# WX0_011_911DL.net
KiCad netlist of a schematic drawn in Altium Designer
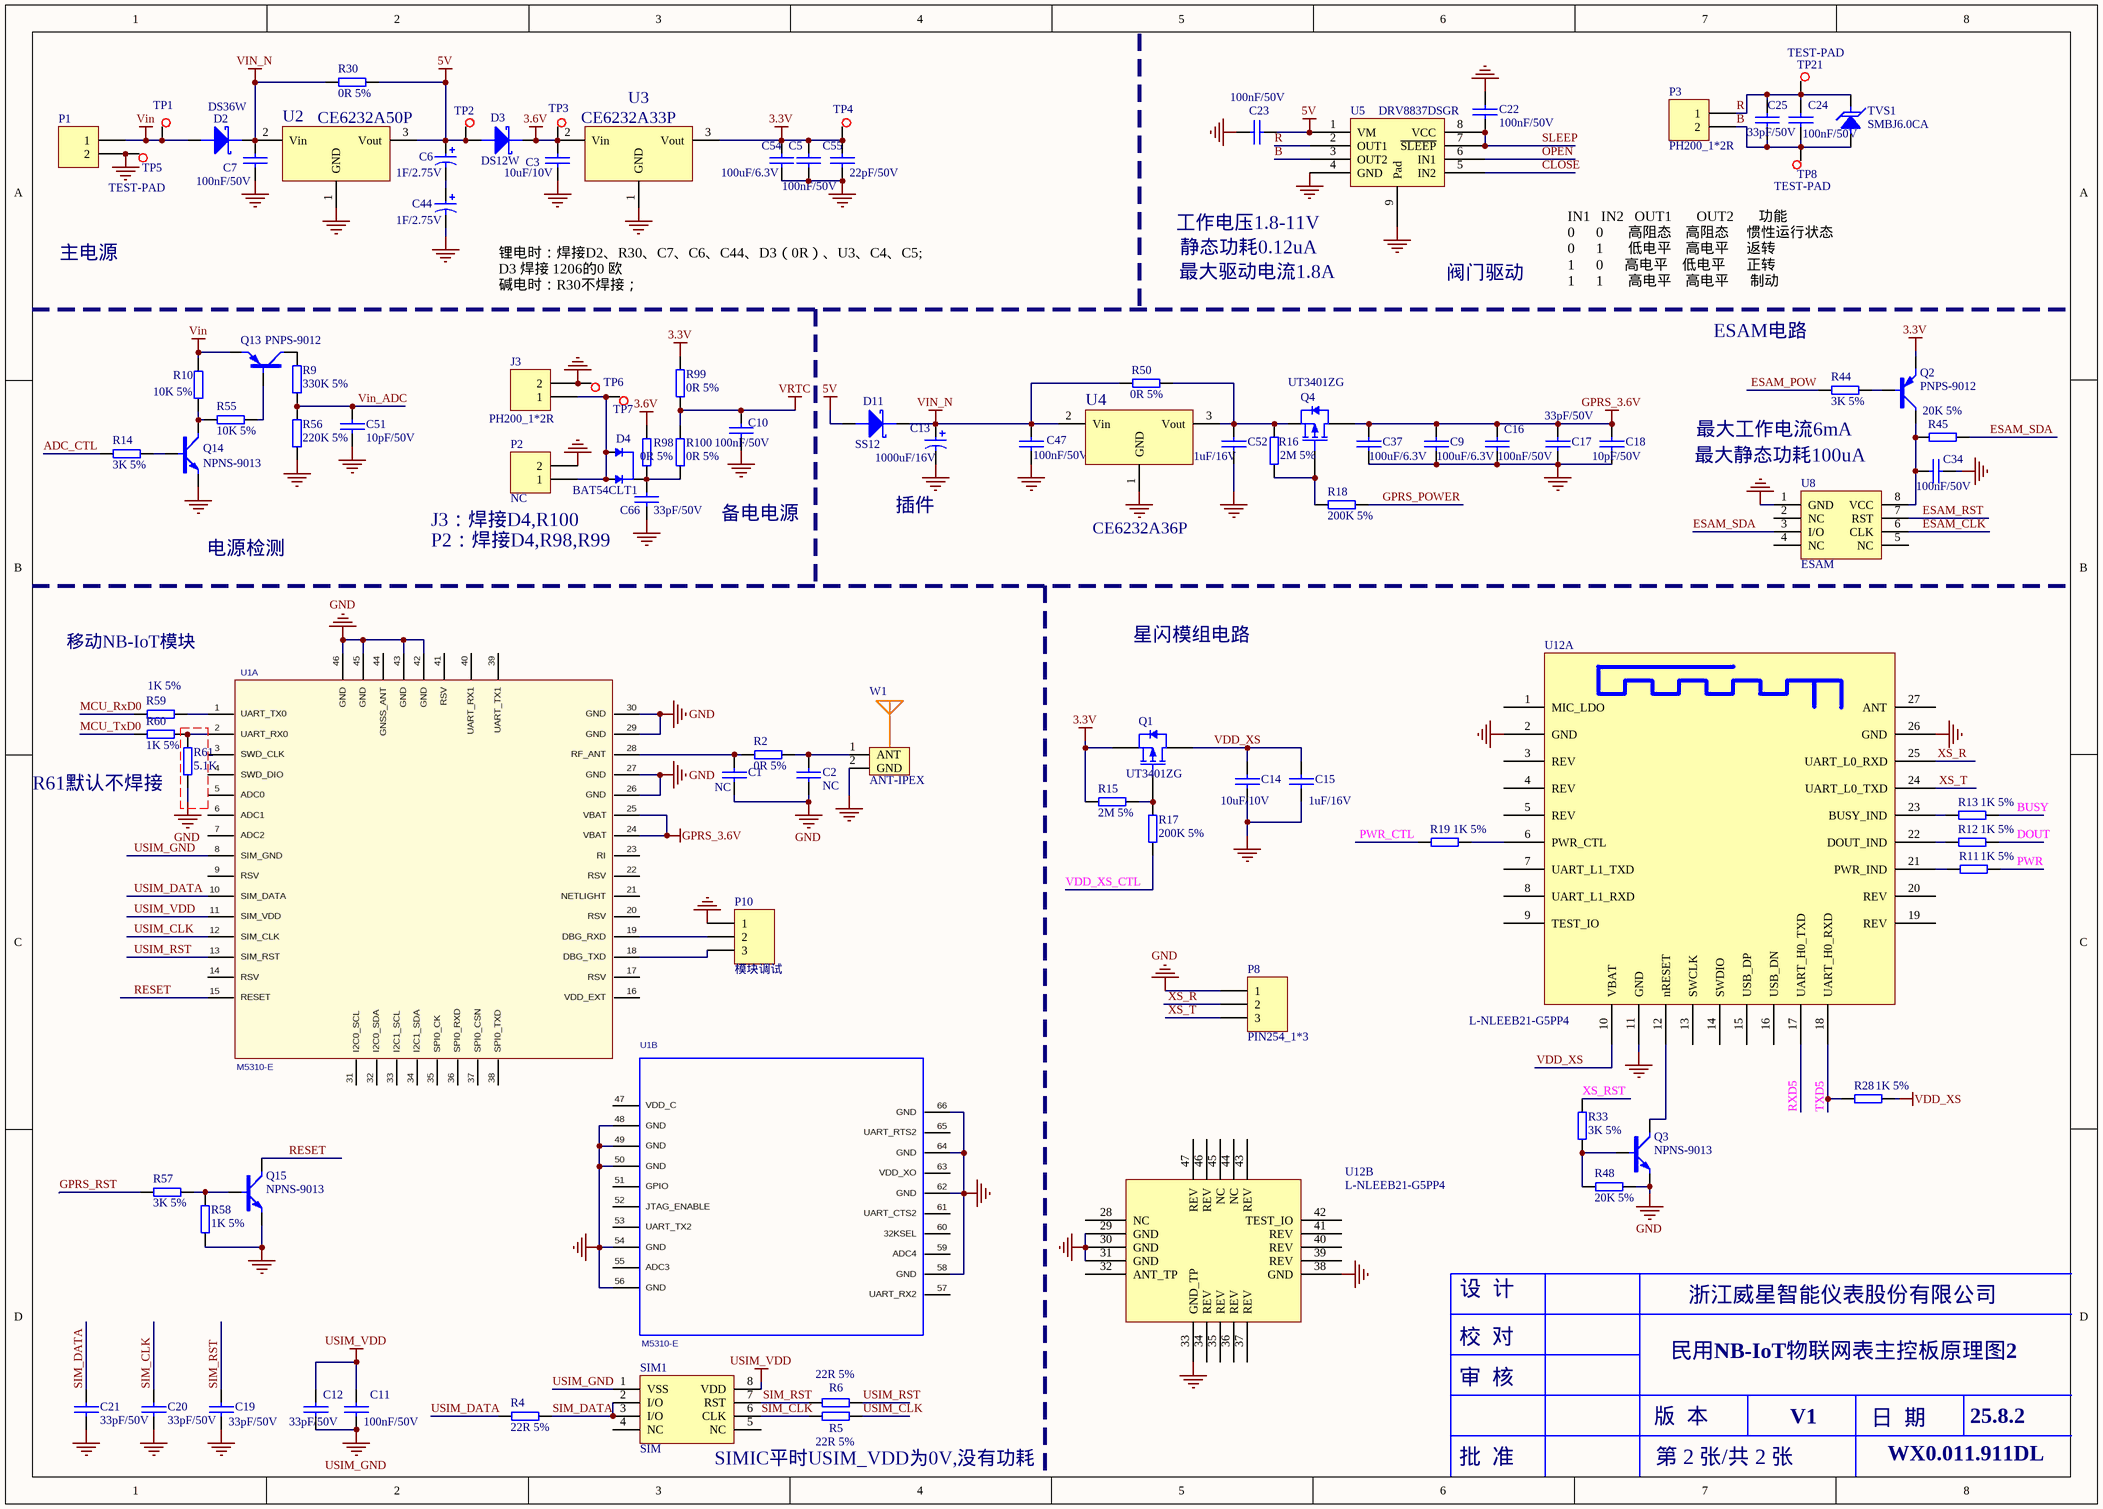
[diagram p0: WX0.011.911DL.SchDoc]

(export (version "E")
  (design (tool "Eeschema 10.0.6"))
  (components
    (comp (ref "C1")
      (value "NC")
      (footprint "CAP0603")
      (description "12P,50 V,±5%,0603,国巨,CC0603JRNPO9BN12")
      (fields (field (name "PART NUMBER") "101020103-0005"))
      (libsource (lib "Database_Libs2") (part "CC03JPO9_12P"))
    )
    (comp (ref "C2")
      (value "NC")
      (footprint "CAP0603")
      (description "12P,50 V,±5%,0603,国巨,CC0603JRNPO9BN12")
      (fields (field (name "PART NUMBER") "101020103-0005"))
      (libsource (lib "Database_Libs2") (part "CC03JPO9_12P"))
    )
    (comp (ref "C3")
      (value "10uF/10V")
      (footprint "CAP0603")
      (description "106pF,10 V,±10%,0603,村田,GRM188R61A106KE47D")
      (fields (field (name "PART NUMBER") "101020103-0026"))
      (libsource (lib "Database_Libs2") (part "CC03K5R6_10U"))
    )
    (comp (ref "C5")
      (value "100nF/50V")
      (footprint "CAP0603")
      (description "104pF,50 V,±10%,0603,国巨,CC0603KRX7R9BB104")
      (fields (field (name "PART NUMBER") "101020103-0021"))
      (libsource (lib "Database_Libs2") (part "CC03K7R9_100N"))
    )
    (comp (ref "C6")
      (value "1F/2.75V")
      (footprint "CAPPC_350_800_1600R")
      (description "1F,2.75 V,-20%~+20%,8mm*16mm,红宝石,2.7 DMC 1 M MY4 8X16")
      (fields (field (name "PART NUMBER") "1010202-0015"))
      (libsource (lib "Database_Libs2") (part "CALM3MRDMC_1F"))
    )
    (comp (ref "C7")
      (value "100nF/50V")
      (footprint "CAP0603")
      (description "104pF,50 V,±10%,0603,国巨,CC0603KRX7R9BB104")
      (fields (field (name "PART NUMBER") "101020103-0021"))
      (libsource (lib "Database_Libs2") (part "CC03K7R9_100N"))
    )
    (comp (ref "C9")
      (value "100uF/6.3V")
      (footprint "GRM1206")
      (description "100uF,6.3 V,±20%,1206,村田,GRM31CR60J107ME39L")
      (fields (field (name "PART NUMBER") "101020101-0020"))
      (libsource (lib "Database_Libs2") (part "CC06M5R5_107P"))
    )
    (comp (ref "C10")
      (value "100nF/50V")
      (footprint "CAP0603")
      (description "104pF,50 V,±10%,0603,国巨,CC0603KRX7R9BB104")
      (fields (field (name "PART NUMBER") "101020103-0021"))
      (libsource (lib "Database_Libs2") (part "CC03K7R9_100N"))
    )
    (comp (ref "C11")
      (value "100nF/50V")
      (footprint "CAP0603")
      (description "104pF,50 V,±10%,0603,国巨,CC0603KRX7R9BB104")
      (fields (field (name "PART NUMBER") "101020103-0021"))
      (libsource (lib "Database_Libs2") (part "CC03K7R9_100N"))
    )
    (comp (ref "C12")
      (value "33pF/50V")
      (footprint "CAP0603")
      (description "33pF,50 V,±10%,0603,国巨,CC0603KRNPO9BN33")
      (fields (field (name "PART NUMBER") "101020103-0027"))
      (libsource (lib "Database_Libs2") (part "CC03KPO9_33P"))
    )
    (comp (ref "C13")
      (value "1000uF/16V")
      (footprint "CAPPC_500_800_2000R")
      (description "1000uF,16 V,±20%,8*20mm,Rubycon,16ZLH1000M")
      (fields (field (name "PART NUMBER") "1010203-0029"))
      (libsource (lib "Database_Libs2") (part "CAL7MRZLH_1000U_R"))
    )
    (comp (ref "C14")
      (value "10uF/10V")
      (footprint "CAP0603")
      (description "106pF,10 V,±10%,0603,村田,GRM188R61A106KE47D")
      (fields (field (name "PART NUMBER") "101020103-0026"))
      (libsource (lib "Database_Libs2") (part "CC03K5R6_10U"))
    )
    (comp (ref "C15")
      (value "1uF/16V")
      (footprint "CAP0603")
      (description "105pF,16 V,±10%,0603,国巨,CC0603KRX7R7BB105")
      (fields (field (name "PART NUMBER") "101020103-0003"))
      (libsource (lib "Database_Libs2") (part "CC03K7R7_1U"))
    )
    (comp (ref "C16")
      (value "100nF/50V")
      (footprint "CAP0603")
      (description "104pF,50 V,±10%,0603,国巨,CC0603KRX7R9BB104")
      (fields (field (name "PART NUMBER") "101020103-0021"))
      (libsource (lib "Database_Libs2") (part "CC03K7R9_100N"))
    )
    (comp (ref "C17")
      (value "33pF/50V")
      (footprint "CAP0603")
      (description "33pF,50 V,±10%,0603,国巨,CC0603KRNPO9BN33")
      (fields (field (name "PART NUMBER") "101020103-0027"))
      (libsource (lib "Database_Libs2") (part "CC03KPO9_33P"))
    )
    (comp (ref "C18")
      (value "10pF/50V")
      (footprint "CAP0603")
      (description "10pF,50 V,±5%,0603,X7R,国巨,CC0603JRNPO9BN100")
      (fields (field (name "PART NUMBER") "101020103-0014"))
      (libsource (lib "Database_Libs2") (part "CC03JPO9_10P"))
    )
    (comp (ref "C19")
      (value "33pF/50V")
      (footprint "CAP0603")
      (description "33pF,50 V,±10%,0603,国巨,CC0603KRNPO9BN33")
      (fields (field (name "PART NUMBER") "101020103-0027"))
      (libsource (lib "Database_Libs2") (part "CC03KPO9_33P"))
    )
    (comp (ref "C20")
      (value "33pF/50V")
      (footprint "CAP0603")
      (description "33pF,50 V,±10%,0603,国巨,CC0603KRNPO9BN33")
      (fields (field (name "PART NUMBER") "101020103-0027"))
      (libsource (lib "Database_Libs2") (part "CC03KPO9_33P"))
    )
    (comp (ref "C21")
      (value "33pF/50V")
      (footprint "CAP0603")
      (description "33pF,50 V,±10%,0603,国巨,CC0603KRNPO9BN33")
      (fields (field (name "PART NUMBER") "101020103-0027"))
      (libsource (lib "Database_Libs2") (part "CC03KPO9_33P"))
    )
    (comp (ref "C22")
      (value "100nF/50V")
      (footprint "CAP0603")
      (description "104pF,50 V,±10%,0603,国巨,CC0603KRX7R9BB104")
      (fields (field (name "PART NUMBER") "101020103-0021"))
      (libsource (lib "Database_Libs2") (part "CC03K7R9_100N"))
    )
    (comp (ref "C23")
      (value "100nF/50V")
      (footprint "CAP0603")
      (description "104pF,50 V,±10%,0603,国巨,CC0603KRX7R9BB104")
      (fields (field (name "PART NUMBER") "101020103-0021"))
      (libsource (lib "Database_Libs2") (part "CC03K7R9_100N"))
    )
    (comp (ref "C24")
      (value "100nF/50V")
      (footprint "CAP0603")
      (description "104pF,50 V,±10%,0603,国巨,CC0603KRX7R9BB104")
      (fields (field (name "PART NUMBER") "101020103-0021"))
      (libsource (lib "Database_Libs2") (part "CC03K7R9_100N"))
    )
    (comp (ref "C25")
      (value "33pF/50V")
      (footprint "CAP0603")
      (description "33pF,50 V,±10%,0603,国巨,CC0603KRNPO9BN33")
      (fields (field (name "PART NUMBER") "101020103-0027"))
      (libsource (lib "Database_Libs2") (part "CC03KPO9_33P"))
    )
    (comp (ref "C34")
      (value "100nF/50V")
      (footprint "CAP0603")
      (description "104pF,50 V,±10%,0603,国巨,CC0603KRX7R9BB104")
      (fields (field (name "PART NUMBER") "101020103-0021"))
      (libsource (lib "Database_Libs2") (part "CC03K7R9_100N"))
    )
    (comp (ref "C37")
      (value "100uF/6.3V")
      (footprint "GRM1206")
      (description "100uF,6.3 V,±20%,1206,村田,GRM31CR60J107ME39L")
      (fields (field (name "PART NUMBER") "101020101-0020"))
      (libsource (lib "Database_Libs2") (part "CC06M5R5_107P"))
    )
    (comp (ref "C44")
      (value "1F/2.75V")
      (footprint "CAPPC_350_800_1600R")
      (description "1F,2.75 V,-20%~+20%,8mm*16mm,红宝石,2.7 DMC 1 M MY4 8X16")
      (fields (field (name "PART NUMBER") "1010202-0015"))
      (libsource (lib "Database_Libs2") (part "CALM3MRDMC_1F"))
    )
    (comp (ref "C47")
      (value "100nF/50V")
      (footprint "CAP0603")
      (description "104pF,50 V,±10%,0603,国巨,CC0603KRX7R9BB104")
      (fields (field (name "PART NUMBER") "101020103-0021"))
      (libsource (lib "Database_Libs2") (part "CC03K7R9_100N"))
    )
    (comp (ref "C51")
      (value "10pF/50V")
      (footprint "CAP0603")
      (description "10pF,50 V,±5%,0603,X7R,国巨,CC0603JRNPO9BN100")
      (fields (field (name "PART NUMBER") "101020103-0014"))
      (libsource (lib "Database_Libs2") (part "CC03JPO9_10P"))
    )
    (comp (ref "C52")
      (value "1uF/16V")
      (footprint "CAP0603")
      (description "105pF,16 V,±10%,0603,国巨,CC0603KRX7R7BB105")
      (fields (field (name "PART NUMBER") "101020103-0003"))
      (libsource (lib "Database_Libs2") (part "CC03K7R7_1U"))
    )
    (comp (ref "C54")
      (value "100uF/6.3V")
      (footprint "GRM1206")
      (description "100uF,6.3 V,±20%,1206,村田,GRM31CR60J107ME39L")
      (fields (field (name "PART NUMBER") "101020101-0020"))
      (libsource (lib "Database_Libs2") (part "CC06M5R5_107P"))
    )
    (comp (ref "C55")
      (value "22pF/50V")
      (footprint "CAP0603")
      (description "22pF,50 V,±5%,0603,国巨,CC0603JRNPO9BN22")
      (fields (field (name "PART NUMBER") "101020103-0009"))
      (libsource (lib "Database_Libs2") (part "CC03JPO9_22P"))
    )
    (comp (ref "C66")
      (value "33pF/50V")
      (footprint "CAP0603")
      (description "33pF,50 V,±10%,0603,国巨,CC0603KRNPO9BN33")
      (fields (field (name "PART NUMBER") "101020103-0027"))
      (libsource (lib "Database_Libs2") (part "CC03KPO9_33P"))
    )
    (comp (ref "D2")
      (value "DS36W")
      (footprint "SOD-123FL")
      (description "DS36W,SOD123-FL,3 A,42 V,60 V,浙江领晨科技有限公司,DS36W")
      (fields (field (name "PART NUMBER") "101040101-0055"))
      (libsource (lib "Database_Libs2") (part "02_DS12W"))
    )
    (comp (ref "D3")
      (value "DS12W")
      (footprint "SOD-123FL")
      (description "DS12W,SOD-123FL,1 A,0.55 V,20 V,领晨科技,DS12W")
      (fields (field (name "PART NUMBER") "101040101-0048"))
      (libsource (lib "Database_Libs2") (part "02_DS12W"))
    )
    (comp (ref "D4")
      (value "BAT54CLT1")
      (footprint "SOT-23")
      (description "BAT54CLT1，SOT23-3,SOT23-3,0.2 A,0.8 V,30 V,安森美,BAT54CLT1")
      (fields (field (name "PART NUMBER") "101040101-0038"))
      (libsource (lib "Database_Libs2") (part "02_BAT54CLT1"))
    )
    (comp (ref "D11")
      (value "SS12")
      (footprint "DO-214AC")
      (description "SS12,DO-214AC,1 A,0.55 V,20 V,昶鑫,SS12")
      (fields (field (name "PART NUMBER") "101040101-0009"))
      (libsource (lib "Database_Libs2") (part "02_SS12"))
    )
    (comp (ref "J3")
      (value "PH200_1*2R")
      (description "2.0-2AW,直插弯座，2PIN，脚间距2mm，带防翘起,公头,单排,2.0-2AW;直插弯座，2PIN,脚间距2mm，带防翘起")
      (fields (field (name "PART NUMBER") "1010902-0105"))
      (libsource (lib "") (part "PH200_1*2R_1"))
    )
    (comp (ref "P1")
      (value "~")
      (footprint "PH200_1*2R_BAT")
      (description "2.0-2AW,直插弯座，2PIN，脚间距2mm，带防翘起,公头,单排,2.0-2AW;直插弯座，2PIN,脚间距2mm，带防翘起")
      (fields (field (name "PART NUMBER") "1010902-0105"))
      (libsource (lib "Database_Libs2") (part "PH200_1*2R"))
    )
    (comp (ref "P2")
      (value "NC")
      (footprint "PH200_1*2R_BAT")
      (description "2.0-2AW,直插弯座，2PIN，脚间距2mm，带防翘起,公头,单排,2.0-2AW;直插弯座，2PIN,脚间距2mm，带防翘起")
      (fields (field (name "PART NUMBER") "1010902-0105"))
      (libsource (lib "") (part "PH200_1*2R_1"))
    )
    (comp (ref "P3")
      (value "PH200_1*2R")
      (footprint "PH200_1*2R")
      (description "2.0-2AW,直插弯座，2PIN，脚间距2mm，带防翘起,公头,单排,2.0-2AW;直插弯座，2PIN,脚间距2mm，带防翘起")
      (fields (field (name "PART NUMBER") "1010902-0105"))
      (libsource (lib "Database_Libs2") (part "PH200_1*2R"))
    )
    (comp (ref "P8")
      (value "PIN254_1*3")
      (footprint "PIN254_1*3*WXHJ")
      (libsource (lib "Connect_WX") (part "PIN254_1*3"))
    )
    (comp (ref "P10")
      (value "模块调试")
      (footprint "PIN254_1*3*WXHJ")
      (description "1*3 ，Φ1.0 ，2.54mm，直脚,无需焊接器件")
      (fields (field (name "PART NUMBER") "AD_WXHJ_PinHeader_04"))
      (libsource (lib "Database_Libs2") (part "PIN254_1*3*WXHJ"))
    )
    (comp (ref "Q1")
      (value "UT3401ZG")
      (footprint "SOT-23")
      (description "UT3401ZG,P-MOS,SOT-23,UTC,UT3401ZG")
      (fields (field (name "PART NUMBER") "101040201-0013"))
      (libsource (lib "Database_Libs2") (part "03_P-UT3401ZG"))
    )
    (comp (ref "Q2")
      (value "PNPS-9012")
      (footprint "SOT-23")
      (description "9012,PNP,SOT-23,JCET;长电,S9012")
      (fields (field (name "PART NUMBER") "101040201-0001"))
      (libsource (lib "Database_Libs2") (part "03_PNPS-9012"))
    )
    (comp (ref "Q3")
      (value "NPNS-9013")
      (footprint "SOT-23")
      (description "9013,NPN,SOT-23,长电,S9013")
      (fields (field (name "PART NUMBER") "101040201-0002"))
      (libsource (lib "Database_Libs2") (part "03_NPNS-9013"))
    )
    (comp (ref "Q4")
      (value "UT3401ZG")
      (footprint "SOT-23")
      (description "UT3401ZG,P-MOS,SOT-23,UTC,UT3401ZG")
      (fields (field (name "PART NUMBER") "101040201-0013"))
      (libsource (lib "Database_Libs2") (part "03_P-UT3401ZG"))
    )
    (comp (ref "Q13")
      (value "PNPS-9012")
      (footprint "SOT-23")
      (description "9012,PNP,SOT-23,JCET;长电,S9012")
      (fields (field (name "PART NUMBER") "101040201-0001"))
      (libsource (lib "Database_Libs2") (part "03_PNPS-9012"))
    )
    (comp (ref "Q14")
      (value "NPNS-9013")
      (footprint "SOT-23")
      (description "9013,NPN,SOT-23,长电,S9013")
      (fields (field (name "PART NUMBER") "101040201-0002"))
      (libsource (lib "Database_Libs2") (part "03_NPNS-9013"))
    )
    (comp (ref "Q15")
      (value "NPNS-9013")
      (footprint "SOT-23")
      (description "9013,NPN,SOT-23,长电,S9013")
      (fields (field (name "PART NUMBER") "101040201-0002"))
      (libsource (lib "Database_Libs2") (part "03_NPNS-9013"))
    )
    (comp (ref "R2")
      (value "0R 5%")
      (footprint "RES0603")
      (description "国巨,±5%,0603,,155 ℃,-55 ℃,RC0603J2-070RL,无铅,200 ppm/℃,1/10W,,0R")
      (fields (field (name "PART NUMBER") "101010103-0001"))
      (libsource (lib "Database_Libs2") (part "RC03J_0R"))
    )
    (comp (ref "R4")
      (value "22R 5%")
      (footprint "RES0603")
      (description "国巨,±5%,0603,,155 ℃,-55 ℃,RC0603JR-0722RL,无铅,200 ppm/℃,1/10W,,22欧")
      (fields (field (name "PART NUMBER") "101010103-0009"))
      (libsource (lib "Database_Libs2") (part "RC03J_22R"))
    )
    (comp (ref "R5")
      (value "22R 5%")
      (footprint "RES0603")
      (description "国巨,±5%,0603,,155 ℃,-55 ℃,RC0603JR-0722RL,无铅,200 ppm/℃,1/10W,,22欧")
      (fields (field (name "PART NUMBER") "101010103-0009"))
      (libsource (lib "Database_Libs2") (part "RC03J_22R"))
    )
    (comp (ref "R6")
      (value "22R 5%")
      (footprint "RES0603")
      (description "国巨,±5%,0603,,155 ℃,-55 ℃,RC0603JR-0722RL,无铅,200 ppm/℃,1/10W,,22欧")
      (fields (field (name "PART NUMBER") "101010103-0009"))
      (libsource (lib "Database_Libs2") (part "RC03J_22R"))
    )
    (comp (ref "R9")
      (value "330K 5%")
      (footprint "RES0603")
      (description "330K,±5%,1/10W,0603,国巨,RC0603JR-07330KL")
      (fields (field (name "PART NUMBER") "101010103-0066"))
      (libsource (lib "Database_Libs2") (part "RC03J_330K"))
    )
    (comp (ref "R10")
      (value "10K 5%")
      (footprint "RES0603")
      (description "国巨,±5%,0603,,155 ℃,-55 ℃,RC0603JR-0710KL,无铅,200 ppm/℃,1/10W,,10K")
      (fields (field (name "PART NUMBER") "101010103-0003"))
      (libsource (lib "Database_Libs2") (part "RC03J_10K"))
    )
    (comp (ref "R11")
      (value "1K 5%")
      (footprint "RES0603")
      (description "1K,±5%,1/10W,0603,国巨,RC0603JR-071KL")
      (fields (field (name "PART NUMBER") "101010103-0008"))
      (libsource (lib "Database_Libs2") (part "RC03J_1K"))
    )
    (comp (ref "R12")
      (value "1K 5%")
      (footprint "RES0603")
      (description "1K,±5%,1/10W,0603,国巨,RC0603JR-071KL")
      (fields (field (name "PART NUMBER") "101010103-0008"))
      (libsource (lib "Database_Libs2") (part "RC03J_1K"))
    )
    (comp (ref "R13")
      (value "1K 5%")
      (footprint "RES0603")
      (description "1K,±5%,1/10W,0603,国巨,RC0603JR-071KL")
      (fields (field (name "PART NUMBER") "101010103-0008"))
      (libsource (lib "Database_Libs2") (part "RC03J_1K"))
    )
    (comp (ref "R14")
      (value "3K 5%")
      (footprint "RES0603")
      (description "国巨,±5%,0603,,155 ℃,-55 ℃,RC0603JR-073KL,无铅,100 ppm/℃,1/10W,,3K")
      (fields (field (name "PART NUMBER") "101010103-0006"))
      (libsource (lib "Database_Libs2") (part "RC03J_3K"))
    )
    (comp (ref "R15")
      (value "2M 5%")
      (footprint "RES0603")
      (description "10K±5%,1/10W,0603")
      (fields (field (name "PART NUMBER") "101010103-0003"))
      (libsource (lib "Database_Libs1") (part "RC03JF_10K"))
    )
    (comp (ref "R16")
      (value "2M 5%")
      (footprint "RES0603")
      (description "国巨,±5%,0603,,155 ℃,-55 ℃,RC0603JR-072ML,含铅,100 ppm/℃,1/10W,,2M")
      (fields (field (name "PART NUMBER") "101010103-0025"))
      (libsource (lib "Database_Libs2") (part "RC03J_2M"))
    )
    (comp (ref "R17")
      (value "200K 5%")
      (footprint "RES0603")
      (description "10K±5%,1/10W,0603")
      (fields (field (name "PART NUMBER") "101010103-0003"))
      (libsource (lib "Database_Libs1") (part "RC03JF_10K"))
    )
    (comp (ref "R18")
      (value "200K 5%")
      (footprint "RES0603")
      (description "200K,±5%,1/10W,0603,国巨,RC0603JR-07200KL")
      (fields (field (name "PART NUMBER") "101010103-0034"))
      (libsource (lib "Database_Libs2") (part "RC03J_200K"))
    )
    (comp (ref "R19")
      (value "1K 5%")
      (footprint "RES0603")
      (description "1K,±5%,1/10W,0603,国巨,RC0603JR-071KL")
      (fields (field (name "PART NUMBER") "101010103-0008"))
      (libsource (lib "Database_Libs2") (part "RC03J_1K"))
    )
    (comp (ref "R28")
      (value "1K 5%")
      (footprint "RES0603")
      (description "1K,±5%,1/10W,0603,国巨,RC0603JR-071KL")
      (fields (field (name "PART NUMBER") "101010103-0008"))
      (libsource (lib "Database_Libs2") (part "RC03J_1K"))
    )
    (comp (ref "R30")
      (value "0R 5%")
      (footprint "RES1206")
      (description "0Ω,±5%,1/4W,1206,国巨,RC1206JR-070RL")
      (fields (field (name "PART NUMBER") "101010101-0013"))
      (libsource (lib "Database_Libs2") (part "RC06J_0R"))
    )
    (comp (ref "R33")
      (value "3K 5%")
      (footprint "RES0603")
      (description "国巨,±5%,0603,,155 ℃,-55 ℃,RC0603JR-073KL,无铅,100 ppm/℃,1/10W,,3K")
      (fields (field (name "PART NUMBER") "101010103-0006"))
      (libsource (lib "Database_Libs2") (part "RC03J_3K"))
    )
    (comp (ref "R44")
      (value "3K 5%")
      (footprint "RES0603")
      (description "国巨,±5%,0603,,155 ℃,-55 ℃,RC0603JR-0710KL,无铅,200 ppm/℃,1/10W,,10K")
      (fields (field (name "PART NUMBER") "101010103-0003"))
      (libsource (lib "Database_Libs2") (part "RC03J_10K"))
    )
    (comp (ref "R45")
      (value "20K 5%")
      (footprint "RES0603")
      (description "国巨,±5%,0603,,155 ℃,-55 ℃,RC0603JR-0720KL,无铅,200 ppm/℃,1/10W,,20K")
      (fields (field (name "PART NUMBER") "101010103-0004"))
      (libsource (lib "Database_Libs2") (part "RC03J_20K"))
    )
    (comp (ref "R48")
      (value "20K 5%")
      (footprint "RES0603")
      (description "国巨,±5%,0603,,155 ℃,-55 ℃,RC0603JR-0720KL,无铅,200 ppm/℃,1/10W,,20K")
      (fields (field (name "PART NUMBER") "101010103-0004"))
      (libsource (lib "Database_Libs2") (part "RC03J_20K"))
    )
    (comp (ref "R50")
      (value "0R 5%")
      (footprint "RES1206")
      (description "0Ω,±5%,1/4W,1206,国巨,RC1206JR-070RL")
      (fields (field (name "PART NUMBER") "101010101-0013"))
      (libsource (lib "Database_Libs2") (part "RC06J_0R"))
    )
    (comp (ref "R55")
      (value "10K 5%")
      (footprint "RES0603")
      (description "国巨,±5%,0603,,155 ℃,-55 ℃,RC0603JR-0710KL,无铅,200 ppm/℃,1/10W,,10K")
      (fields (field (name "PART NUMBER") "101010103-0003"))
      (libsource (lib "Database_Libs2") (part "RC03J_10K"))
    )
    (comp (ref "R56")
      (value "220K 5%")
      (footprint "RES0603")
      (description "220K,±5%,1/10W,0603,国巨,RC0603JR-07220KL")
      (fields (field (name "PART NUMBER") "101010103-0044"))
      (libsource (lib "Database_Libs2") (part "RC03J_220K"))
    )
    (comp (ref "R57")
      (value "3K 5%")
      (footprint "RES0603")
      (description "国巨,±5%,0603,,155 ℃,-55 ℃,RC0603JR-073KL,无铅,100 ppm/℃,1/10W,,3K")
      (fields (field (name "PART NUMBER") "101010103-0006"))
      (libsource (lib "Database_Libs2") (part "RC03J_3K"))
    )
    (comp (ref "R58")
      (value "1K 5%")
      (footprint "RES0603")
      (description "1K,±5%,1/10W,0603,国巨,RC0603JR-071KL")
      (fields (field (name "PART NUMBER") "101010103-0008"))
      (libsource (lib "Database_Libs2") (part "RC03J_1K"))
    )
    (comp (ref "R59")
      (value "1K 5%")
      (footprint "RES0603")
      (description "1K,±5%,1/10W,0603,国巨,RC0603JR-071KL")
      (fields (field (name "PART NUMBER") "101010103-0008"))
      (libsource (lib "Database_Libs2") (part "RC03J_1K"))
    )
    (comp (ref "R60")
      (value "1K 5%")
      (footprint "RES0603")
      (description "国巨,±5%,0603,,155 ℃,-55 ℃,RC0603JR-0720KL,无铅,200 ppm/℃,1/10W,,20K")
      (fields (field (name "PART NUMBER") "101010103-0004"))
      (libsource (lib "Database_Libs2") (part "RC03J_20K"))
    )
    (comp (ref "R61")
      (value "5.1K")
      (footprint "RES0603")
      (description "国巨,±5%,0603,,155 ℃,-55 ℃,RC0603JR-0720KL,无铅,200 ppm/℃,1/10W,,20K")
      (fields (field (name "PART NUMBER") "101010103-0004"))
      (libsource (lib "Database_Libs2") (part "RC03J_20K"))
    )
    (comp (ref "R98")
      (value "0R 5%")
      (footprint "RES0603")
      (description "0Ω,±5%,1/4W,1206,国巨,RC1206JR-070RL")
      (fields (field (name "PART NUMBER") "101010101-0013"))
      (libsource (lib "Database_Libs2") (part "RC06J_0R"))
    )
    (comp (ref "R99")
      (value "0R 5%")
      (footprint "RES0603")
      (description "0Ω,±5%,1/4W,1206,国巨,RC1206JR-070RL")
      (fields (field (name "PART NUMBER") "101010101-0013"))
      (libsource (lib "Database_Libs2") (part "RC06J_0R"))
    )
    (comp (ref "R100")
      (value "0R 5%")
      (footprint "RES0603")
      (description "0Ω,±5%,1/4W,1206,国巨,RC1206JR-070RL")
      (fields (field (name "PART NUMBER") "101010101-0013"))
      (libsource (lib "Database_Libs2") (part "RC06J_0R"))
    )
    (comp (ref "SIM1") (value "SIM") (footprint "SIMIC") (libsource (lib "Chip_WX") (part "05_SIMIC")))
    (comp (ref "TP1")
      (value "TEST-PAD")
      (footprint "TEST-PAD")
      (description "单面焊盘测试点")
      (fields (field (name "PART NUMBER") "AD_WXHJ_TEST-PAD_01"))
      (libsource (lib "Database_Libs2") (part "TEST-PAD"))
    )
    (comp (ref "TP2")
      (value "TEST-PAD")
      (footprint "TEST-PAD")
      (description "单面焊盘测试点")
      (fields (field (name "PART NUMBER") "AD_WXHJ_TEST-PAD_01"))
      (libsource (lib "Database_Libs2") (part "TEST-PAD"))
    )
    (comp (ref "TP3")
      (value "TEST-PAD")
      (footprint "TEST-PAD")
      (description "单面焊盘测试点")
      (fields (field (name "PART NUMBER") "AD_WXHJ_TEST-PAD_01"))
      (libsource (lib "Database_Libs2") (part "TEST-PAD"))
    )
    (comp (ref "TP4")
      (value "TEST-PAD")
      (footprint "TEST-PAD")
      (description "单面焊盘测试点")
      (fields (field (name "PART NUMBER") "AD_WXHJ_TEST-PAD_01"))
      (libsource (lib "Database_Libs2") (part "TEST-PAD"))
    )
    (comp (ref "TP5")
      (value "TEST-PAD")
      (footprint "TEST-PAD")
      (description "单面焊盘测试点")
      (fields (field (name "PART NUMBER") "AD_WXHJ_TEST-PAD_01"))
      (libsource (lib "Database_Libs2") (part "TEST-PAD"))
    )
    (comp (ref "TP6")
      (value "TEST-PAD")
      (footprint "TEST-PAD")
      (description "单面焊盘测试点")
      (fields (field (name "PART NUMBER") "AD_WXHJ_TEST-PAD_01"))
      (libsource (lib "Database_Libs2") (part "TEST-PAD"))
    )
    (comp (ref "TP7")
      (value "TEST-PAD")
      (footprint "TEST-PAD")
      (description "单面焊盘测试点")
      (fields (field (name "PART NUMBER") "AD_WXHJ_TEST-PAD_01"))
      (libsource (lib "Database_Libs2") (part "TEST-PAD"))
    )
    (comp (ref "TP8")
      (value "TEST-PAD")
      (footprint "TEST-PAD")
      (description "单面焊盘测试点")
      (fields (field (name "PART NUMBER") "AD_WXHJ_TEST-PAD_01"))
      (libsource (lib "Database_Libs2") (part "TEST-PAD"))
    )
    (comp (ref "TP21")
      (value "TEST-PAD")
      (footprint "TEST-PAD")
      (description "单面焊盘测试点")
      (fields (field (name "PART NUMBER") "AD_WXHJ_TEST-PAD_01"))
      (libsource (lib "Database_Libs2") (part "TEST-PAD"))
    )
    (comp (ref "TVS1")
      (value "SMBJ6.0CA")
      (footprint "DO-214AA")
      (description "SMBJ6.0CA,DO-214AA,10.3 V,6.0 V,600 W,58.3 A,800 uA,上海君耀电子有限公司,SMBJ6.0CA")
      (fields (field (name "PART NUMBER") "101040101-0024"))
      (libsource (lib "Database_Libs2") (part "05_SMBJ6.0CA"))
    )
    (comp (ref "U1")
      (value "M5310-E")
      (footprint "MOD_M5310EV")
      (description "Module_M5310EV_0.9mm")
      (fields (field (name "MANUFACTURER") "Module_M5310EV"))
      (libsource (lib "M5310-E") (part "MOD_M5310EV_LGA66P"))
    )
    (comp (ref "U2")
      (value "CE6232A50P")
      (footprint "SOT-89")
      (fields (field (name "PART NUMBER") "1010503-0013"))
      (libsource (lib "Database_Libs2") (part "02_S-1206B50-U3"))
    )
    (comp (ref "U3")
      (value "CE6232A33P")
      (footprint "SOT-89")
      (fields (field (name "PART NUMBER") "1010503-0002"))
      (libsource (lib "Database_Libs2") (part "02_S-1206B33-U3T1G"))
    )
    (comp (ref "U4")
      (value "CE6232A36P")
      (footprint "SOT-89")
      (description "CE6232A36P,CE6232A36P,SOT89-3,8 V,1.8 V,0.11 V,3.6 V,600mA,0.8 uA,南京芯力微电子有限公司")
      (fields (field (name "PART NUMBER") "1010503-0031"))
      (libsource (lib "Database_Libs2") (part "02_CE6232A36P"))
    )
    (comp (ref "U5")
      (value "DRV8837DSGR")
      (footprint "S-PWSON-N8")
      (description "DRV8837DSGR,S-PWSON-N8,TI,DRV8837DSGR")
      (fields (field (name "PART NUMBER") "101050101-0060"))
      (libsource (lib "Database_Libs2") (part "07_DRV8837DSGR"))
    )
    (comp (ref "U8") (value "ESAM") (libsource (lib "Chip_WX") (part "04_ESAM")))
    (comp (ref "U12")
      (value "L-NLEEB21-G5PP4")
      (footprint "WX0.010.983PCB-4.21:L-NLEEB21-G5BP4")
      (libsource (lib "L-NLEEB21-G5BP4_V03") (part "L-NLEEB21-G5BP4"))
    )
    (comp (ref "W1")
      (value "ANT-IPEX")
      (footprint "ANT-IPEX")
      (description "IPEX，配GPRS天线转接线")
      (fields (field (name "PART NUMBER") "1010902-0053"))
      (libsource (lib "Database_Libs2") (part "IPEX"))
    )
  )
  (nets
    (net (code "1") (name "/ADC_CTL") (class "Default")
      (node (ref "R14") (pin "1") (pinfunction "1_1") (pintype "passive"))
    )
    (net (code "2") (name "/B") (class "Default")
      (node (ref "C24") (pin "2") (pinfunction "2_2") (pintype "passive"))
      (node (ref "C25") (pin "2") (pinfunction "2_2") (pintype "passive"))
      (node (ref "P3") (pin "2") (pinfunction "2_2") (pintype "passive"))
      (node (ref "TP8") (pin "1") (pinfunction "1_1") (pintype "passive"))
      (node (ref "TVS1") (pin "1") (pinfunction "1_1") (pintype "passive"))
      (node (ref "U5") (pin "3") (pinfunction "OUT2_3") (pintype "passive"))
    )
    (net (code "3") (name "/BUSY") (class "Default")
      (node (ref "R13") (pin "1") (pinfunction "1_1") (pintype "passive"))
    )
    (net (code "4") (name "/CLOSE") (class "Default")
      (node (ref "U5") (pin "5") (pinfunction "IN2_5") (pintype "passive"))
    )
    (net (code "5") (name "/DOUT") (class "Default")
      (node (ref "R12") (pin "1") (pinfunction "1_1") (pintype "passive"))
    )
    (net (code "6") (name "/ESAM_CLK") (class "Default")
      (node (ref "U8") (pin "6") (pinfunction "CLK_6") (pintype "passive"))
    )
    (net (code "7") (name "/ESAM_POW") (class "Default")
      (node (ref "R44") (pin "1") (pinfunction "1_1") (pintype "passive"))
    )
    (net (code "8") (name "/ESAM_RST") (class "Default")
      (node (ref "U8") (pin "7") (pinfunction "RST_7") (pintype "passive"))
    )
    (net (code "9") (name "/ESAM_SDA") (class "Default")
      (node (ref "R45") (pin "2") (pinfunction "2_2") (pintype "passive"))
      (node (ref "U8") (pin "3") (pinfunction "I/O_3") (pintype "passive"))
    )
    (net (code "10") (name "/GPRS_POWER") (class "Default")
      (node (ref "R18") (pin "1") (pinfunction "1_1") (pintype "passive"))
    )
    (net (code "11") (name "/GPRS_RST") (class "Default")
      (node (ref "R57") (pin "1") (pinfunction "1_1") (pintype "passive"))
    )
    (net (code "12") (name "/MCU_RxD0") (class "Default")
      (node (ref "R59") (pin "1") (pinfunction "1_1") (pintype "passive"))
    )
    (net (code "13") (name "/MCU_TxD0") (class "Default")
      (node (ref "R60") (pin "1") (pinfunction "1_1") (pintype "passive"))
    )
    (net (code "14") (name "/OPEN") (class "Default")
      (node (ref "U5") (pin "6") (pinfunction "IN1_6") (pintype "passive"))
    )
    (net (code "15") (name "/PWR") (class "Default")
      (node (ref "R11") (pin "1") (pinfunction "1_1") (pintype "passive"))
    )
    (net (code "16") (name "/PWR_CTL") (class "Default")
      (node (ref "R19") (pin "2") (pinfunction "2_2") (pintype "passive"))
    )
    (net (code "17") (name "/R") (class "Default")
      (node (ref "C24") (pin "1") (pinfunction "1_1") (pintype "passive"))
      (node (ref "C25") (pin "1") (pinfunction "1_1") (pintype "passive"))
      (node (ref "P3") (pin "1") (pinfunction "1_1") (pintype "passive"))
      (node (ref "TP21") (pin "1") (pinfunction "1_1") (pintype "passive"))
      (node (ref "TVS1") (pin "2") (pinfunction "2_2") (pintype "passive"))
      (node (ref "U5") (pin "2") (pinfunction "OUT1_2") (pintype "passive"))
    )
    (net (code "18") (name "/RESET") (class "Default")
      (node (ref "Q15") (pin "3") (pinfunction "C_3") (pintype "passive"))
      (node (ref "U1") (pin "15") (pinfunction "RESET_15") (pintype "passive"))
    )
    (net (code "19") (name "/RXD5") (class "Default")
      (node (ref "U12") (pin "17") (pinfunction "UART_H0_TXD_17") (pintype "passive"))
    )
    (net (code "20") (name "/SIM_CLK") (class "Default")
      (node (ref "C20") (pin "1") (pinfunction "1_1") (pintype "passive"))
      (node (ref "R5") (pin "1") (pinfunction "1_1") (pintype "passive"))
      (node (ref "SIM1") (pin "6") (pinfunction "CLK_6") (pintype "passive"))
    )
    (net (code "21") (name "/SIM_DATA") (class "Default")
      (node (ref "C21") (pin "1") (pinfunction "1_1") (pintype "passive"))
      (node (ref "R4") (pin "2") (pinfunction "2_2") (pintype "passive"))
      (node (ref "SIM1") (pin "2") (pinfunction "I/O_2") (pintype "passive"))
      (node (ref "SIM1") (pin "3") (pinfunction "I/O_3") (pintype "passive"))
    )
    (net (code "22") (name "/SIM_RST") (class "Default")
      (node (ref "C19") (pin "1") (pinfunction "1_1") (pintype "passive"))
      (node (ref "R6") (pin "1") (pinfunction "1_1") (pintype "passive"))
      (node (ref "SIM1") (pin "7") (pinfunction "RST_7") (pintype "passive"))
    )
    (net (code "23") (name "/SLEEP") (class "Default")
      (node (ref "C22") (pin "2") (pinfunction "2_2") (pintype "passive"))
      (node (ref "U5") (pin "7") (pinfunction "~{SLEEP}_7") (pintype "passive"))
      (node (ref "U5") (pin "8") (pinfunction "VCC_8") (pintype "passive"))
    )
    (net (code "24") (name "/TXD5") (class "Default")
      (node (ref "R28") (pin "2") (pinfunction "2_2") (pintype "passive"))
      (node (ref "U12") (pin "18") (pinfunction "UART_H0_RXD_18") (pintype "passive"))
    )
    (net (code "25") (name "/USIM_CLK") (class "Default")
      (node (ref "R5") (pin "2") (pinfunction "2_2") (pintype "passive"))
      (node (ref "U1") (pin "12") (pinfunction "SIM_CLK_12") (pintype "passive"))
    )
    (net (code "26") (name "/USIM_DATA") (class "Default")
      (node (ref "R4") (pin "1") (pinfunction "1_1") (pintype "passive"))
      (node (ref "U1") (pin "10") (pinfunction "SIM_DATA_10") (pintype "passive"))
    )
    (net (code "27") (name "/USIM_RST") (class "Default")
      (node (ref "R6") (pin "2") (pinfunction "2_2") (pintype "passive"))
      (node (ref "U1") (pin "13") (pinfunction "SIM_RST_13") (pintype "passive"))
    )
    (net (code "28") (name "/VDD_XS_CTL") (class "Default")
      (node (ref "R17") (pin "1") (pinfunction "1_1") (pintype "passive"))
    )
    (net (code "29") (name "/Vin_ADC") (class "Default")
      (node (ref "C51") (pin "2") (pinfunction "2_2") (pintype "passive"))
      (node (ref "R56") (pin "1") (pinfunction "1_1") (pintype "passive"))
      (node (ref "R9") (pin "2") (pinfunction "2_2") (pintype "passive"))
    )
    (net (code "30") (name "/XS_R") (class "Default")
      (node (ref "P8") (pin "2") (pinfunction "2_2") (pintype "passive"))
      (node (ref "U12") (pin "25") (pinfunction "UART_L0_RXD_25") (pintype "passive"))
    )
    (net (code "31") (name "/XS_RST") (class "Default")
      (node (ref "R33") (pin "1") (pinfunction "1_1") (pintype "passive"))
    )
    (net (code "32") (name "/XS_T") (class "Default")
      (node (ref "P8") (pin "3") (pinfunction "3_3") (pintype "passive"))
      (node (ref "U12") (pin "24") (pinfunction "UART_L0_TXD_24") (pintype "passive"))
    )
    (net (code "33") (name "3.3V") (class "Default")
      (node (ref "C5") (pin "1") (pinfunction "1_1") (pintype "passive"))
      (node (ref "C54") (pin "2") (pinfunction "2_2") (pintype "passive"))
      (node (ref "C55") (pin "1") (pinfunction "1_1") (pintype "passive"))
      (node (ref "Q1") (pin "2") (pinfunction "S_2") (pintype "passive"))
      (node (ref "Q2") (pin "2") (pinfunction "E_2") (pintype "passive"))
      (node (ref "R15") (pin "1") (pinfunction "1_1") (pintype "passive"))
      (node (ref "R99") (pin "2") (pinfunction "2_2") (pintype "passive"))
      (node (ref "TP4") (pin "1") (pinfunction "1_1") (pintype "passive"))
      (node (ref "U3") (pin "3") (pinfunction "Vout_3") (pintype "passive"))
    )
    (net (code "34") (name "3.6V") (class "Default")
      (node (ref "C3") (pin "1") (pinfunction "1_1") (pintype "passive"))
      (node (ref "D3") (pin "2") (pinfunction "2_2") (pintype "passive"))
      (node (ref "R98") (pin "2") (pinfunction "2_2") (pintype "passive"))
      (node (ref "TP3") (pin "1") (pinfunction "1_1") (pintype "passive"))
      (node (ref "U3") (pin "2") (pinfunction "Vin_2") (pintype "passive"))
    )
    (net (code "35") (name "5V") (class "Default")
      (node (ref "C23") (pin "2") (pinfunction "2_2") (pintype "passive"))
      (node (ref "C6") (pin "1") (pinfunction "1_1") (pintype "passive"))
      (node (ref "D11") (pin "1") (pinfunction "1_1") (pintype "passive"))
      (node (ref "D3") (pin "1") (pinfunction "1_1") (pintype "passive"))
      (node (ref "R30") (pin "2") (pinfunction "2_2") (pintype "passive"))
      (node (ref "TP2") (pin "1") (pinfunction "1_1") (pintype "passive"))
      (node (ref "U2") (pin "3") (pinfunction "Vout_3") (pintype "passive"))
      (node (ref "U5") (pin "1") (pinfunction "VM_1") (pintype "passive"))
    )
    (net (code "36") (name "GND") (class "Default")
      (node (ref "C1") (pin "1") (pinfunction "1_1") (pintype "passive"))
      (node (ref "C10") (pin "2") (pinfunction "2_2") (pintype "passive"))
      (node (ref "C13") (pin "2") (pinfunction "2_2") (pintype "passive"))
      (node (ref "C14") (pin "2") (pinfunction "2_2") (pintype "passive"))
      (node (ref "C15") (pin "2") (pinfunction "2_2") (pintype "passive"))
      (node (ref "C16") (pin "2") (pinfunction "2_2") (pintype "passive"))
      (node (ref "C17") (pin "2") (pinfunction "2_2") (pintype "passive"))
      (node (ref "C18") (pin "1") (pinfunction "1_1") (pintype "passive"))
      (node (ref "C19") (pin "2") (pinfunction "2_2") (pintype "passive"))
      (node (ref "C2") (pin "1") (pinfunction "1_1") (pintype "passive"))
      (node (ref "C20") (pin "2") (pinfunction "2_2") (pintype "passive"))
      (node (ref "C21") (pin "2") (pinfunction "2_2") (pintype "passive"))
      (node (ref "C22") (pin "1") (pinfunction "1_1") (pintype "passive"))
      (node (ref "C23") (pin "1") (pinfunction "1_1") (pintype "passive"))
      (node (ref "C3") (pin "2") (pinfunction "2_2") (pintype "passive"))
      (node (ref "C34") (pin "2") (pinfunction "2_2") (pintype "passive"))
      (node (ref "C37") (pin "2") (pinfunction "2_2") (pintype "passive"))
      (node (ref "C44") (pin "2") (pinfunction "2_2") (pintype "passive"))
      (node (ref "C47") (pin "2") (pinfunction "2_2") (pintype "passive"))
      (node (ref "C5") (pin "2") (pinfunction "2_2") (pintype "passive"))
      (node (ref "C51") (pin "1") (pinfunction "1_1") (pintype "passive"))
      (node (ref "C52") (pin "2") (pinfunction "2_2") (pintype "passive"))
      (node (ref "C54") (pin "1") (pinfunction "1_1") (pintype "passive"))
      (node (ref "C55") (pin "2") (pinfunction "2_2") (pintype "passive"))
      (node (ref "C66") (pin "2") (pinfunction "2_2") (pintype "passive"))
      (node (ref "C7") (pin "2") (pinfunction "2_2") (pintype "passive"))
      (node (ref "C9") (pin "2") (pinfunction "2_2") (pintype "passive"))
      (node (ref "J3") (pin "2") (pinfunction "2_2") (pintype "passive"))
      (node (ref "P1") (pin "2") (pinfunction "2_2") (pintype "passive"))
      (node (ref "P10") (pin "1") (pinfunction "1_1") (pintype "passive"))
      (node (ref "P2") (pin "2") (pinfunction "2_2") (pintype "passive"))
      (node (ref "P8") (pin "1") (pinfunction "1_1") (pintype "passive"))
      (node (ref "Q14") (pin "2") (pinfunction "E_2") (pintype "passive"))
      (node (ref "Q15") (pin "2") (pinfunction "E_2") (pintype "passive"))
      (node (ref "Q3") (pin "2") (pinfunction "E_2") (pintype "passive"))
      (node (ref "R48") (pin "2") (pinfunction "2_2") (pintype "passive"))
      (node (ref "R56") (pin "2") (pinfunction "2_2") (pintype "passive"))
      (node (ref "R58") (pin "1") (pinfunction "1_1") (pintype "passive"))
      (node (ref "R61") (pin "2") (pinfunction "2_2") (pintype "passive"))
      (node (ref "TP5") (pin "1") (pinfunction "1_1") (pintype "passive"))
      (node (ref "TP6") (pin "1") (pinfunction "1_1") (pintype "passive"))
      (node (ref "U1") (pin "26") (pinfunction "GND_26") (pintype "passive"))
      (node (ref "U1") (pin "27") (pinfunction "GND_27") (pintype "passive"))
      (node (ref "U1") (pin "29") (pinfunction "GND_29") (pintype "passive"))
      (node (ref "U1") (pin "30") (pinfunction "GND_30") (pintype "passive"))
      (node (ref "U1") (pin "42") (pinfunction "GND_42") (pintype "passive"))
      (node (ref "U1") (pin "43") (pinfunction "GND_43") (pintype "passive"))
      (node (ref "U1") (pin "45") (pinfunction "GND_45") (pintype "passive"))
      (node (ref "U1") (pin "46") (pinfunction "GND_46") (pintype "passive"))
      (node (ref "U1") (pin "48") (pinfunction "GND_48") (pintype "passive"))
      (node (ref "U1") (pin "49") (pinfunction "GND_49") (pintype "passive"))
      (node (ref "U1") (pin "50") (pinfunction "GND_50") (pintype "passive"))
      (node (ref "U1") (pin "54") (pinfunction "GND_54") (pintype "passive"))
      (node (ref "U1") (pin "56") (pinfunction "GND_56") (pintype "passive"))
      (node (ref "U1") (pin "58") (pinfunction "GND_58") (pintype "passive"))
      (node (ref "U1") (pin "62") (pinfunction "GND_62") (pintype "passive"))
      (node (ref "U1") (pin "64") (pinfunction "GND_64") (pintype "passive"))
      (node (ref "U1") (pin "66") (pinfunction "GND_66") (pintype "passive"))
      (node (ref "U12") (pin "11") (pinfunction "GND_11") (pintype "passive"))
      (node (ref "U12") (pin "2") (pinfunction "GND_2") (pintype "passive"))
      (node (ref "U12") (pin "26") (pinfunction "GND_26") (pintype "passive"))
      (node (ref "U12") (pin "29") (pinfunction "GND_29") (pintype "passive"))
      (node (ref "U12") (pin "30") (pinfunction "GND_30") (pintype "passive"))
      (node (ref "U12") (pin "31") (pinfunction "GND_31") (pintype "passive"))
      (node (ref "U12") (pin "33") (pinfunction "GND_TP_33") (pintype "passive"))
      (node (ref "U12") (pin "38") (pinfunction "GND_38") (pintype "passive"))
      (node (ref "U2") (pin "1") (pinfunction "GND_1") (pintype "passive"))
      (node (ref "U3") (pin "1") (pinfunction "GND_1") (pintype "passive"))
      (node (ref "U4") (pin "1") (pinfunction "GND_1") (pintype "passive"))
      (node (ref "U5") (pin "4") (pinfunction "GND_4") (pintype "passive"))
      (node (ref "U5") (pin "9") (pinfunction "Pad_9") (pintype "passive"))
      (node (ref "U8") (pin "1") (pinfunction "GND_1") (pintype "passive"))
      (node (ref "W1") (pin "2") (pinfunction "GND_2") (pintype "passive"))
    )
    (net (code "37") (name "GPRS_3.6V") (class "Default")
      (node (ref "C16") (pin "1") (pinfunction "1_1") (pintype "passive"))
      (node (ref "C17") (pin "1") (pinfunction "1_1") (pintype "passive"))
      (node (ref "C18") (pin "2") (pinfunction "2_2") (pintype "passive"))
      (node (ref "C37") (pin "1") (pinfunction "1_1") (pintype "passive"))
      (node (ref "C9") (pin "1") (pinfunction "1_1") (pintype "passive"))
      (node (ref "Q4") (pin "3") (pinfunction "D_3") (pintype "passive"))
      (node (ref "U1") (pin "24") (pinfunction "VBAT_24") (pintype "passive"))
      (node (ref "U1") (pin "25") (pinfunction "VBAT_25") (pintype "passive"))
    )
    (net (code "38") (name "Net-(C44-Pad1)") (class "Default")
      (node (ref "C44") (pin "1") (pinfunction "1_1") (pintype "passive"))
      (node (ref "C6") (pin "2") (pinfunction "2_2") (pintype "passive"))
    )
    (net (code "39") (name "Net-(D4-A-Pad1)") (class "Default")
      (node (ref "D4") (pin "1") (pinfunction "A_1") (pintype "passive"))
      (node (ref "D4") (pin "2") (pinfunction "A_2") (pintype "passive"))
      (node (ref "J3") (pin "1") (pinfunction "1_1") (pintype "passive"))
      (node (ref "P2") (pin "1") (pinfunction "1_1") (pintype "passive"))
      (node (ref "TP7") (pin "1") (pinfunction "1_1") (pintype "passive"))
    )
    (net (code "40") (name "Net-(D4-C)") (class "Default")
      (node (ref "C66") (pin "1") (pinfunction "1_1") (pintype "passive"))
      (node (ref "D4") (pin "3") (pinfunction "C_3") (pintype "passive"))
      (node (ref "R100") (pin "1") (pinfunction "1_1") (pintype "passive"))
      (node (ref "R98") (pin "1") (pinfunction "1_1") (pintype "passive"))
    )
    (net (code "41") (name "Net-(Q1-G)") (class "Default")
      (node (ref "Q1") (pin "1") (pinfunction "G_1") (pintype "passive"))
      (node (ref "R15") (pin "2") (pinfunction "2_2") (pintype "passive"))
      (node (ref "R17") (pin "2") (pinfunction "2_2") (pintype "passive"))
    )
    (net (code "42") (name "Net-(Q2-B)") (class "Default")
      (node (ref "Q2") (pin "1") (pinfunction "B_1") (pintype "passive"))
      (node (ref "R44") (pin "2") (pinfunction "2_2") (pintype "passive"))
    )
    (net (code "43") (name "Net-(Q2-C)") (class "Default")
      (node (ref "C34") (pin "1") (pinfunction "1_1") (pintype "passive"))
      (node (ref "Q2") (pin "3") (pinfunction "C_3") (pintype "passive"))
      (node (ref "R45") (pin "1") (pinfunction "1_1") (pintype "passive"))
      (node (ref "U8") (pin "8") (pinfunction "VCC_8") (pintype "passive"))
    )
    (net (code "44") (name "Net-(Q3-B)") (class "Default")
      (node (ref "Q3") (pin "1") (pinfunction "B_1") (pintype "passive"))
      (node (ref "R33") (pin "2") (pinfunction "2_2") (pintype "passive"))
      (node (ref "R48") (pin "1") (pinfunction "1_1") (pintype "passive"))
    )
    (net (code "45") (name "Net-(Q3-C)") (class "Default")
      (node (ref "Q3") (pin "3") (pinfunction "C_3") (pintype "passive"))
      (node (ref "U12") (pin "12") (pinfunction "nRESET_12") (pintype "passive"))
    )
    (net (code "46") (name "Net-(Q4-G)") (class "Default")
      (node (ref "Q4") (pin "1") (pinfunction "G_1") (pintype "passive"))
      (node (ref "R16") (pin "1") (pinfunction "1_1") (pintype "passive"))
      (node (ref "R18") (pin "2") (pinfunction "2_2") (pintype "passive"))
    )
    (net (code "47") (name "Net-(Q4-S)") (class "Default")
      (node (ref "C52") (pin "1") (pinfunction "1_1") (pintype "passive"))
      (node (ref "Q4") (pin "2") (pinfunction "S_2") (pintype "passive"))
      (node (ref "R16") (pin "2") (pinfunction "2_2") (pintype "passive"))
      (node (ref "R50") (pin "2") (pinfunction "2_2") (pintype "passive"))
      (node (ref "U4") (pin "3") (pinfunction "Vout_3") (pintype "passive"))
    )
    (net (code "48") (name "Net-(Q13-B)") (class "Default")
      (node (ref "Q13") (pin "1") (pinfunction "B_1") (pintype "passive"))
      (node (ref "R55") (pin "2") (pinfunction "2_2") (pintype "passive"))
    )
    (net (code "49") (name "Net-(Q13-C)") (class "Default")
      (node (ref "Q13") (pin "3") (pinfunction "C_3") (pintype "passive"))
      (node (ref "R9") (pin "1") (pinfunction "1_1") (pintype "passive"))
    )
    (net (code "50") (name "Net-(Q14-B)") (class "Default")
      (node (ref "Q14") (pin "1") (pinfunction "B_1") (pintype "passive"))
      (node (ref "R14") (pin "2") (pinfunction "2_2") (pintype "passive"))
    )
    (net (code "51") (name "Net-(Q14-C)") (class "Default")
      (node (ref "Q14") (pin "3") (pinfunction "C_3") (pintype "passive"))
      (node (ref "R10") (pin "1") (pinfunction "1_1") (pintype "passive"))
      (node (ref "R55") (pin "1") (pinfunction "1_1") (pintype "passive"))
    )
    (net (code "52") (name "Net-(Q15-B)") (class "Default")
      (node (ref "Q15") (pin "1") (pinfunction "B_1") (pintype "passive"))
      (node (ref "R57") (pin "2") (pinfunction "2_2") (pintype "passive"))
      (node (ref "R58") (pin "2") (pinfunction "2_2") (pintype "passive"))
    )
    (net (code "53") (name "Net-(U1A-DBG_RXD)") (class "Default")
      (node (ref "P10") (pin "2") (pinfunction "2_2") (pintype "passive"))
      (node (ref "U1") (pin "19") (pinfunction "DBG_RXD_19") (pintype "passive"))
    )
    (net (code "54") (name "Net-(U1A-DBG_TXD)") (class "Default")
      (node (ref "P10") (pin "3") (pinfunction "3_3") (pintype "passive"))
      (node (ref "U1") (pin "18") (pinfunction "DBG_TXD_18") (pintype "passive"))
    )
    (net (code "55") (name "Net-(U1A-RF_ANT)") (class "Default")
      (node (ref "C1") (pin "2") (pinfunction "2_2") (pintype "passive"))
      (node (ref "R2") (pin "2") (pinfunction "2_2") (pintype "passive"))
      (node (ref "U1") (pin "28") (pinfunction "RF_ANT_28") (pintype "passive"))
    )
    (net (code "56") (name "Net-(U1A-UART_RX0)") (class "Default")
      (node (ref "R60") (pin "2") (pinfunction "2_2") (pintype "passive"))
      (node (ref "R61") (pin "1") (pinfunction "1_1") (pintype "passive"))
      (node (ref "U1") (pin "2") (pinfunction "UART_RX0_2") (pintype "passive"))
    )
    (net (code "57") (name "Net-(U1A-UART_TX0)") (class "Default")
      (node (ref "R59") (pin "2") (pinfunction "2_2") (pintype "passive"))
      (node (ref "U1") (pin "1") (pinfunction "UART_TX0_1") (pintype "passive"))
    )
    (net (code "58") (name "Net-(U12A-BUSY_IND)") (class "Default")
      (node (ref "R13") (pin "2") (pinfunction "2_2") (pintype "passive"))
      (node (ref "U12") (pin "23") (pinfunction "BUSY_IND_23") (pintype "passive"))
    )
    (net (code "59") (name "Net-(U12A-DOUT_IND)") (class "Default")
      (node (ref "R12") (pin "2") (pinfunction "2_2") (pintype "passive"))
      (node (ref "U12") (pin "22") (pinfunction "DOUT_IND_22") (pintype "passive"))
    )
    (net (code "60") (name "Net-(U12A-PWR_CTL)") (class "Default")
      (node (ref "R19") (pin "1") (pinfunction "1_1") (pintype "passive"))
      (node (ref "U12") (pin "6") (pinfunction "PWR_CTL_6") (pintype "passive"))
    )
    (net (code "61") (name "Net-(U12A-PWR_IND)") (class "Default")
      (node (ref "R11") (pin "2") (pinfunction "2_2") (pintype "passive"))
      (node (ref "U12") (pin "21") (pinfunction "PWR_IND_21") (pintype "passive"))
    )
    (net (code "62") (name "Net-(W1-ANT)") (class "Default")
      (node (ref "C2") (pin "2") (pinfunction "2_2") (pintype "passive"))
      (node (ref "R2") (pin "1") (pinfunction "1_1") (pintype "passive"))
      (node (ref "W1") (pin "1") (pinfunction "ANT_1") (pintype "passive"))
    )
    (net (code "63") (name "USIM_GND") (class "Default")
      (node (ref "C11") (pin "2") (pinfunction "2_2") (pintype "passive"))
      (node (ref "C12") (pin "2") (pinfunction "2_2") (pintype "passive"))
      (node (ref "SIM1") (pin "1") (pinfunction "VSS_1") (pintype "passive"))
      (node (ref "U1") (pin "8") (pinfunction "SIM_GND_8") (pintype "passive"))
    )
    (net (code "64") (name "USIM_VDD") (class "Default")
      (node (ref "C11") (pin "1") (pinfunction "1_1") (pintype "passive"))
      (node (ref "C12") (pin "1") (pinfunction "1_1") (pintype "passive"))
      (node (ref "SIM1") (pin "8") (pinfunction "VDD_8") (pintype "passive"))
      (node (ref "U1") (pin "11") (pinfunction "SIM_VDD_11") (pintype "passive"))
    )
    (net (code "65") (name "VDD_XS") (class "Default")
      (node (ref "C14") (pin "1") (pinfunction "1_1") (pintype "passive"))
      (node (ref "C15") (pin "1") (pinfunction "1_1") (pintype "passive"))
      (node (ref "Q1") (pin "3") (pinfunction "D_3") (pintype "passive"))
      (node (ref "R28") (pin "1") (pinfunction "1_1") (pintype "passive"))
      (node (ref "U12") (pin "10") (pinfunction "VBAT_10") (pintype "passive"))
    )
    (net (code "66") (name "VIN_N") (class "Default")
      (node (ref "C13") (pin "1") (pinfunction "1_1") (pintype "passive"))
      (node (ref "C47") (pin "1") (pinfunction "1_1") (pintype "passive"))
      (node (ref "C7") (pin "1") (pinfunction "1_1") (pintype "passive"))
      (node (ref "D11") (pin "2") (pinfunction "2_2") (pintype "passive"))
      (node (ref "D2") (pin "2") (pinfunction "2_2") (pintype "passive"))
      (node (ref "R30") (pin "1") (pinfunction "1_1") (pintype "passive"))
      (node (ref "R50") (pin "1") (pinfunction "1_1") (pintype "passive"))
      (node (ref "U2") (pin "2") (pinfunction "Vin_2") (pintype "passive"))
      (node (ref "U4") (pin "2") (pinfunction "Vin_2") (pintype "passive"))
    )
    (net (code "67") (name "VRTC") (class "Default")
      (node (ref "C10") (pin "1") (pinfunction "1_1") (pintype "passive"))
      (node (ref "R100") (pin "2") (pinfunction "2_2") (pintype "passive"))
      (node (ref "R99") (pin "1") (pinfunction "1_1") (pintype "passive"))
    )
    (net (code "68") (name "Vin") (class "Default")
      (node (ref "D2") (pin "1") (pinfunction "1_1") (pintype "passive"))
      (node (ref "P1") (pin "1") (pinfunction "1_1") (pintype "passive"))
      (node (ref "Q13") (pin "2") (pinfunction "E_2") (pintype "passive"))
      (node (ref "R10") (pin "2") (pinfunction "2_2") (pintype "passive"))
      (node (ref "TP1") (pin "1") (pinfunction "1_1") (pintype "passive"))
    )
    (net (code "69") (name "unconnected-(SIM1-NC-Pad4)") (class "Default")
      (node (ref "SIM1") (pin "4") (pinfunction "NC_4") (pintype "passive"))
    )
    (net (code "70") (name "unconnected-(SIM1-NC-Pad5)") (class "Default")
      (node (ref "SIM1") (pin "5") (pinfunction "NC_5") (pintype "passive"))
    )
    (net (code "71") (name "unconnected-(U1A-ADC0-Pad5)") (class "Default")
      (node (ref "U1") (pin "5") (pinfunction "ADC0_5") (pintype "passive"))
    )
    (net (code "72") (name "unconnected-(U1A-ADC1-Pad6)") (class "Default")
      (node (ref "U1") (pin "6") (pinfunction "ADC1_6") (pintype "passive"))
    )
    (net (code "73") (name "unconnected-(U1A-ADC2-Pad7)") (class "Default")
      (node (ref "U1") (pin "7") (pinfunction "ADC2_7") (pintype "passive"))
    )
    (net (code "74") (name "unconnected-(U1A-GNSS_ANT-Pad44)") (class "Default")
      (node (ref "U1") (pin "44") (pinfunction "GNSS_ANT_44") (pintype "passive"))
    )
    (net (code "75") (name "unconnected-(U1A-I2C0_SCL-Pad31)") (class "Default")
      (node (ref "U1") (pin "31") (pinfunction "I2C0_SCL_31") (pintype "passive"))
    )
    (net (code "76") (name "unconnected-(U1A-I2C0_SDA-Pad32)") (class "Default")
      (node (ref "U1") (pin "32") (pinfunction "I2C0_SDA_32") (pintype "passive"))
    )
    (net (code "77") (name "unconnected-(U1A-I2C1_SCL-Pad33)") (class "Default")
      (node (ref "U1") (pin "33") (pinfunction "I2C1_SCL_33") (pintype "passive"))
    )
    (net (code "78") (name "unconnected-(U1A-I2C1_SDA-Pad34)") (class "Default")
      (node (ref "U1") (pin "34") (pinfunction "I2C1_SDA_34") (pintype "passive"))
    )
    (net (code "79") (name "unconnected-(U1A-NETLIGHT-Pad21)") (class "Default")
      (node (ref "U1") (pin "21") (pinfunction "NETLIGHT_21") (pintype "passive"))
    )
    (net (code "80") (name "unconnected-(U1A-RI-Pad23)") (class "Default")
      (node (ref "U1") (pin "23") (pinfunction "RI_23") (pintype "passive"))
    )
    (net (code "81") (name "unconnected-(U1A-RSV-Pad9)") (class "Default")
      (node (ref "U1") (pin "9") (pinfunction "RSV_9") (pintype "passive"))
    )
    (net (code "82") (name "unconnected-(U1A-RSV-Pad14)") (class "Default")
      (node (ref "U1") (pin "14") (pinfunction "RSV_14") (pintype "passive"))
    )
    (net (code "83") (name "unconnected-(U1A-RSV-Pad17)") (class "Default")
      (node (ref "U1") (pin "17") (pinfunction "RSV_17") (pintype "passive"))
    )
    (net (code "84") (name "unconnected-(U1A-RSV-Pad20)") (class "Default")
      (node (ref "U1") (pin "20") (pinfunction "RSV_20") (pintype "passive"))
    )
    (net (code "85") (name "unconnected-(U1A-RSV-Pad22)") (class "Default")
      (node (ref "U1") (pin "22") (pinfunction "RSV_22") (pintype "passive"))
    )
    (net (code "86") (name "unconnected-(U1A-RSV-Pad41)") (class "Default")
      (node (ref "U1") (pin "41") (pinfunction "RSV_41") (pintype "passive"))
    )
    (net (code "87") (name "unconnected-(U1A-SPI0_CK-Pad35)") (class "Default")
      (node (ref "U1") (pin "35") (pinfunction "SPI0_CK_35") (pintype "passive"))
    )
    (net (code "88") (name "unconnected-(U1A-SPI0_CSN-Pad37)") (class "Default")
      (node (ref "U1") (pin "37") (pinfunction "SPI0_CSN_37") (pintype "passive"))
    )
    (net (code "89") (name "unconnected-(U1A-SPI0_RXD-Pad36)") (class "Default")
      (node (ref "U1") (pin "36") (pinfunction "SPI0_RXD_36") (pintype "passive"))
    )
    (net (code "90") (name "unconnected-(U1A-SPI0_TXD-Pad38)") (class "Default")
      (node (ref "U1") (pin "38") (pinfunction "SPI0_TXD_38") (pintype "passive"))
    )
    (net (code "91") (name "unconnected-(U1A-SWD_CLK-Pad3)") (class "Default")
      (node (ref "U1") (pin "3") (pinfunction "SWD_CLK_3") (pintype "passive"))
    )
    (net (code "92") (name "unconnected-(U1A-SWD_DIO-Pad4)") (class "Default")
      (node (ref "U1") (pin "4") (pinfunction "SWD_DIO_4") (pintype "passive"))
    )
    (net (code "93") (name "unconnected-(U1A-UART_RX1-Pad40)") (class "Default")
      (node (ref "U1") (pin "40") (pinfunction "UART_RX1_40") (pintype "passive"))
    )
    (net (code "94") (name "unconnected-(U1A-UART_TX1-Pad39)") (class "Default")
      (node (ref "U1") (pin "39") (pinfunction "UART_TX1_39") (pintype "passive"))
    )
    (net (code "95") (name "unconnected-(U1A-VDD_EXT-Pad16)") (class "Default")
      (node (ref "U1") (pin "16") (pinfunction "VDD_EXT_16") (pintype "passive"))
    )
    (net (code "96") (name "unconnected-(U1B-32KSEL-Pad60)") (class "Default")
      (node (ref "U1") (pin "60") (pinfunction "32KSEL_60") (pintype "passive"))
    )
    (net (code "97") (name "unconnected-(U1B-ADC3-Pad55)") (class "Default")
      (node (ref "U1") (pin "55") (pinfunction "ADC3_55") (pintype "passive"))
    )
    (net (code "98") (name "unconnected-(U1B-ADC4-Pad59)") (class "Default")
      (node (ref "U1") (pin "59") (pinfunction "ADC4_59") (pintype "passive"))
    )
    (net (code "99") (name "unconnected-(U1B-GPIO-Pad51)") (class "Default")
      (node (ref "U1") (pin "51") (pinfunction "GPIO_51") (pintype "passive"))
    )
    (net (code "100") (name "unconnected-(U1B-JTAG_ENABLE-Pad52)") (class "Default")
      (node (ref "U1") (pin "52") (pinfunction "JTAG_ENABLE_52") (pintype "passive"))
    )
    (net (code "101") (name "unconnected-(U1B-UART_CTS2-Pad61)") (class "Default")
      (node (ref "U1") (pin "61") (pinfunction "UART_CTS2_61") (pintype "passive"))
    )
    (net (code "102") (name "unconnected-(U1B-UART_RTS2-Pad65)") (class "Default")
      (node (ref "U1") (pin "65") (pinfunction "UART_RTS2_65") (pintype "passive"))
    )
    (net (code "103") (name "unconnected-(U1B-UART_RX2-Pad57)") (class "Default")
      (node (ref "U1") (pin "57") (pinfunction "UART_RX2_57") (pintype "passive"))
    )
    (net (code "104") (name "unconnected-(U1B-UART_TX2-Pad53)") (class "Default")
      (node (ref "U1") (pin "53") (pinfunction "UART_TX2_53") (pintype "passive"))
    )
    (net (code "105") (name "unconnected-(U1B-VDD_C-Pad47)") (class "Default")
      (node (ref "U1") (pin "47") (pinfunction "VDD_C_47") (pintype "passive"))
    )
    (net (code "106") (name "unconnected-(U1B-VDD_XO-Pad63)") (class "Default")
      (node (ref "U1") (pin "63") (pinfunction "VDD_XO_63") (pintype "passive"))
    )
    (net (code "107") (name "unconnected-(U8-NC-Pad2)") (class "Default")
      (node (ref "U8") (pin "2") (pinfunction "NC_2") (pintype "passive"))
    )
    (net (code "108") (name "unconnected-(U8-NC-Pad4)") (class "Default")
      (node (ref "U8") (pin "4") (pinfunction "NC_4") (pintype "passive"))
    )
    (net (code "109") (name "unconnected-(U8-NC-Pad5)") (class "Default")
      (node (ref "U8") (pin "5") (pinfunction "NC_5") (pintype "passive"))
    )
    (net (code "110") (name "unconnected-(U12A-ANT-Pad27)") (class "Default")
      (node (ref "U12") (pin "27") (pinfunction "ANT_27") (pintype "passive"))
    )
    (net (code "111") (name "unconnected-(U12A-MIC_LDO-Pad1)") (class "Default")
      (node (ref "U12") (pin "1") (pinfunction "MIC_LDO_1") (pintype "passive"))
    )
    (net (code "112") (name "unconnected-(U12A-REV-Pad3)") (class "Default")
      (node (ref "U12") (pin "3") (pinfunction "REV_3") (pintype "passive"))
    )
    (net (code "113") (name "unconnected-(U12A-REV-Pad4)") (class "Default")
      (node (ref "U12") (pin "4") (pinfunction "REV_4") (pintype "passive"))
    )
    (net (code "114") (name "unconnected-(U12A-REV-Pad5)") (class "Default")
      (node (ref "U12") (pin "5") (pinfunction "REV_5") (pintype "passive"))
    )
    (net (code "115") (name "unconnected-(U12A-REV-Pad19)") (class "Default")
      (node (ref "U12") (pin "19") (pinfunction "REV_19") (pintype "passive"))
    )
    (net (code "116") (name "unconnected-(U12A-REV-Pad20)") (class "Default")
      (node (ref "U12") (pin "20") (pinfunction "REV_20") (pintype "passive"))
    )
    (net (code "117") (name "unconnected-(U12A-SWCLK-Pad13)") (class "Default")
      (node (ref "U12") (pin "13") (pinfunction "SWCLK_13") (pintype "passive"))
    )
    (net (code "118") (name "unconnected-(U12A-SWDIO-Pad14)") (class "Default")
      (node (ref "U12") (pin "14") (pinfunction "SWDIO_14") (pintype "passive"))
    )
    (net (code "119") (name "unconnected-(U12A-TEST_IO-Pad9)") (class "Default")
      (node (ref "U12") (pin "9") (pinfunction "TEST_IO_9") (pintype "passive"))
    )
    (net (code "120") (name "unconnected-(U12A-UART_L1_RXD-Pad8)") (class "Default")
      (node (ref "U12") (pin "8") (pinfunction "UART_L1_RXD_8") (pintype "passive"))
    )
    (net (code "121") (name "unconnected-(U12A-UART_L1_TXD-Pad7)") (class "Default")
      (node (ref "U12") (pin "7") (pinfunction "UART_L1_TXD_7") (pintype "passive"))
    )
    (net (code "122") (name "unconnected-(U12A-USB_DN-Pad16)") (class "Default")
      (node (ref "U12") (pin "16") (pinfunction "USB_DN_16") (pintype "passive"))
    )
    (net (code "123") (name "unconnected-(U12A-USB_DP-Pad15)") (class "Default")
      (node (ref "U12") (pin "15") (pinfunction "USB_DP_15") (pintype "passive"))
    )
    (net (code "124") (name "unconnected-(U12B-ANT_TP-Pad32)") (class "Default")
      (node (ref "U12") (pin "32") (pinfunction "ANT_TP_32") (pintype "passive"))
    )
    (net (code "125") (name "unconnected-(U12B-NC-Pad28)") (class "Default")
      (node (ref "U12") (pin "28") (pinfunction "NC_28") (pintype "passive"))
    )
    (net (code "126") (name "unconnected-(U12B-NC-Pad44)") (class "Default")
      (node (ref "U12") (pin "44") (pinfunction "NC_44") (pintype "passive"))
    )
    (net (code "127") (name "unconnected-(U12B-NC-Pad45)") (class "Default")
      (node (ref "U12") (pin "45") (pinfunction "NC_45") (pintype "passive"))
    )
    (net (code "128") (name "unconnected-(U12B-REV-Pad34)") (class "Default")
      (node (ref "U12") (pin "34") (pinfunction "REV_34") (pintype "passive"))
    )
    (net (code "129") (name "unconnected-(U12B-REV-Pad35)") (class "Default")
      (node (ref "U12") (pin "35") (pinfunction "REV_35") (pintype "passive"))
    )
    (net (code "130") (name "unconnected-(U12B-REV-Pad36)") (class "Default")
      (node (ref "U12") (pin "36") (pinfunction "REV_36") (pintype "passive"))
    )
    (net (code "131") (name "unconnected-(U12B-REV-Pad37)") (class "Default")
      (node (ref "U12") (pin "37") (pinfunction "REV_37") (pintype "passive"))
    )
    (net (code "132") (name "unconnected-(U12B-REV-Pad39)") (class "Default")
      (node (ref "U12") (pin "39") (pinfunction "REV_39") (pintype "passive"))
    )
    (net (code "133") (name "unconnected-(U12B-REV-Pad40)") (class "Default")
      (node (ref "U12") (pin "40") (pinfunction "REV_40") (pintype "passive"))
    )
    (net (code "134") (name "unconnected-(U12B-REV-Pad41)") (class "Default")
      (node (ref "U12") (pin "41") (pinfunction "REV_41") (pintype "passive"))
    )
    (net (code "135") (name "unconnected-(U12B-REV-Pad43)") (class "Default")
      (node (ref "U12") (pin "43") (pinfunction "REV_43") (pintype "passive"))
    )
    (net (code "136") (name "unconnected-(U12B-REV-Pad46)") (class "Default")
      (node (ref "U12") (pin "46") (pinfunction "REV_46") (pintype "passive"))
    )
    (net (code "137") (name "unconnected-(U12B-REV-Pad47)") (class "Default")
      (node (ref "U12") (pin "47") (pinfunction "REV_47") (pintype "passive"))
    )
    (net (code "138") (name "unconnected-(U12B-TEST_IO-Pad42)") (class "Default")
      (node (ref "U12") (pin "42") (pinfunction "TEST_IO_42") (pintype "passive"))
    )
  )
)
